# apprino.net
KiCad netlist of a schematic drawn in EAGLE
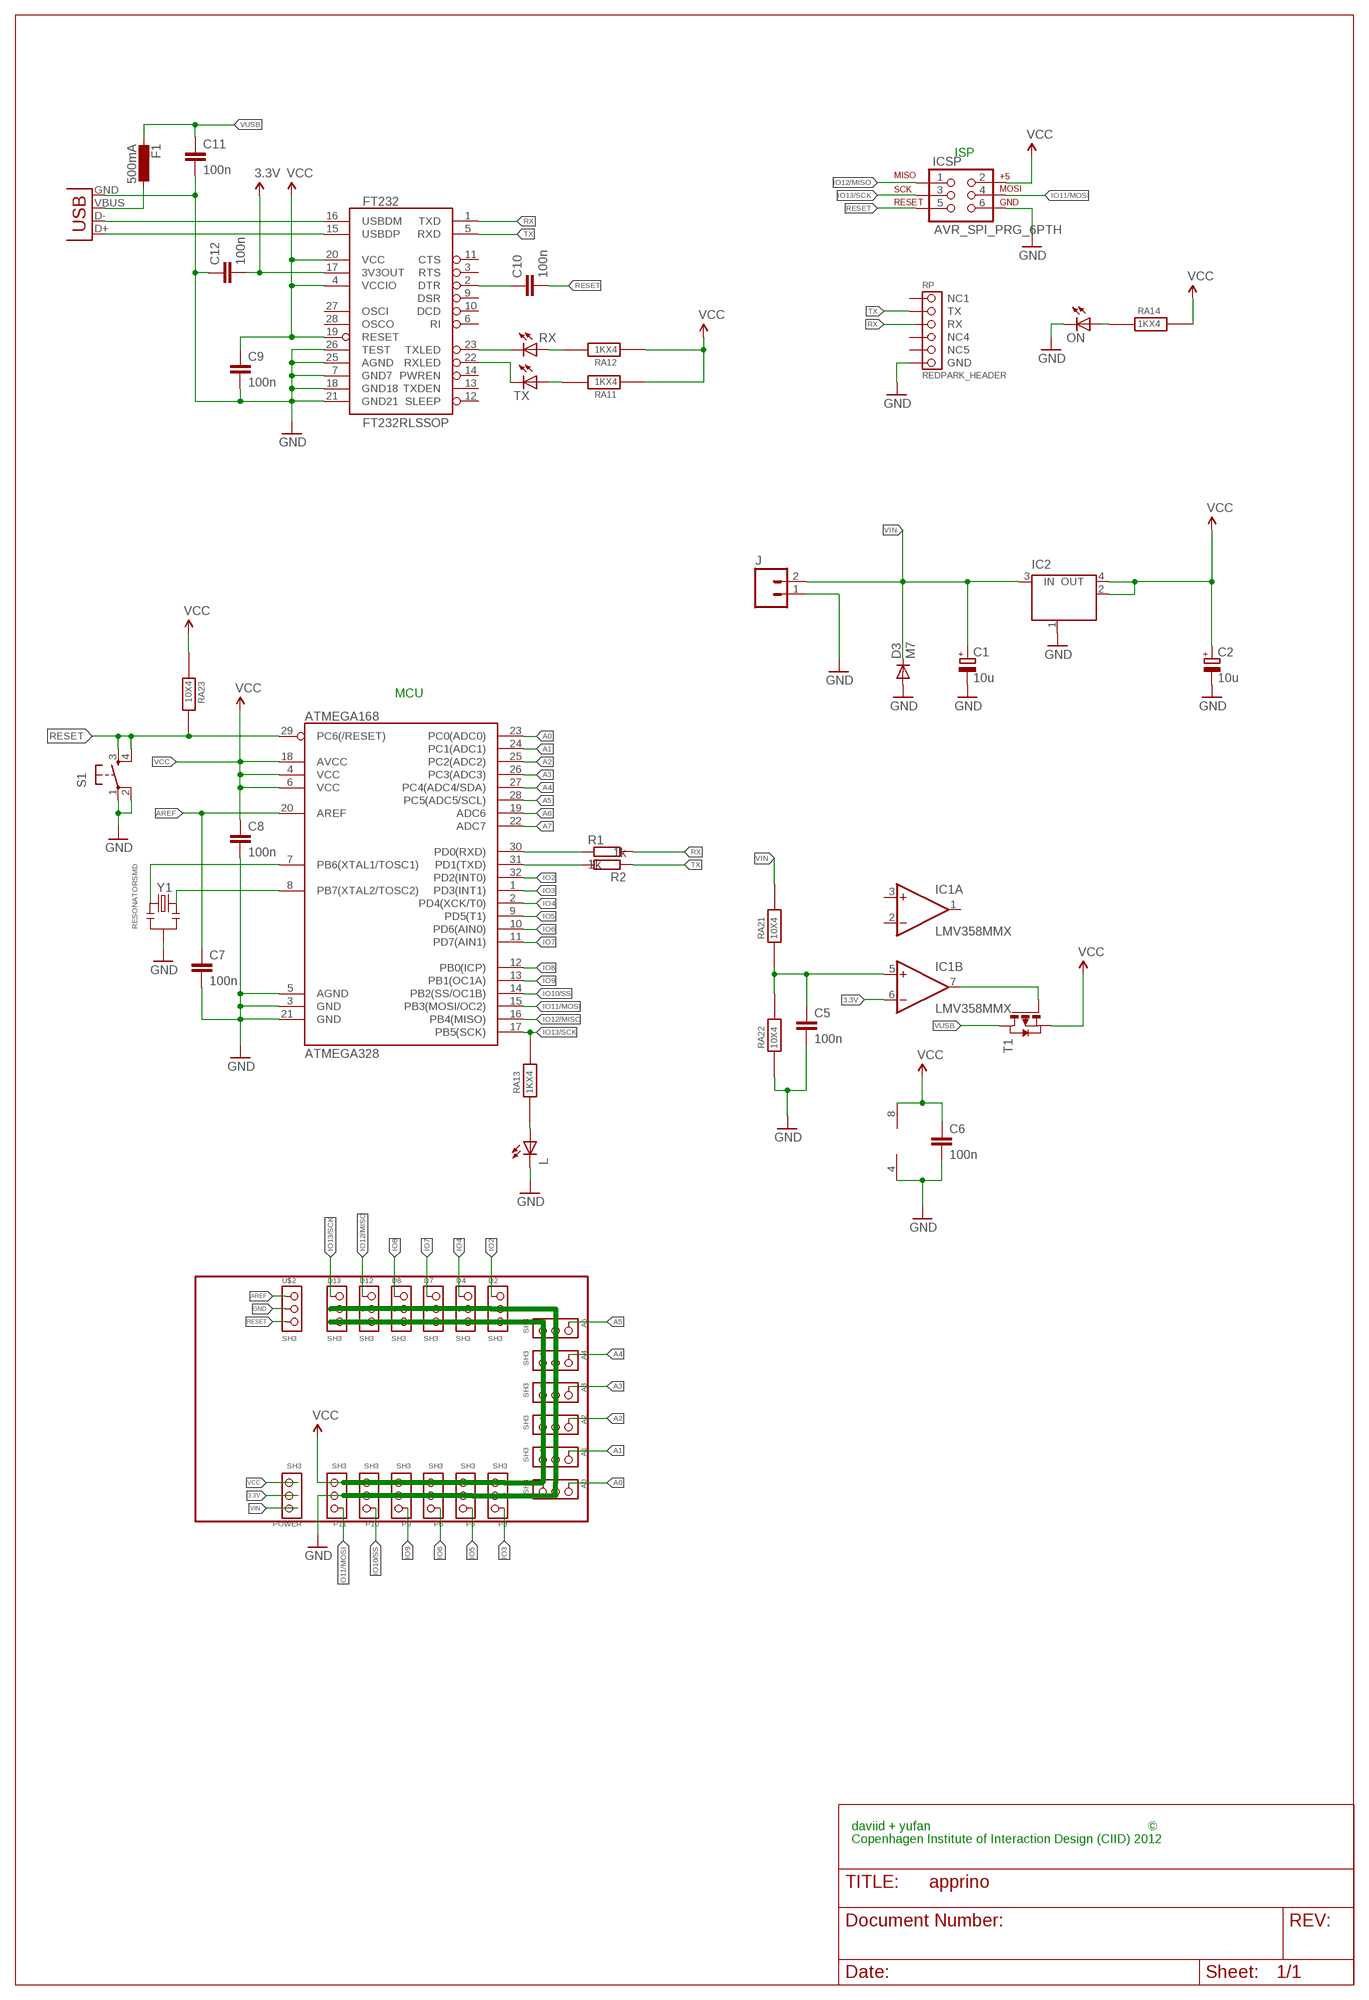
[diagram p0: schematic, sheet 1]

(export (version "E")
  (design (tool "Eeschema 10.0.6"))
  (components
    (comp (ref "A0")
      (value "SH3")
      (footprint "eagle-import:SH3")
      (libsource (lib "eagle-import") (part "SH3"))
    )
    (comp (ref "A1")
      (value "SH3")
      (footprint "eagle-import:SH3")
      (libsource (lib "eagle-import") (part "SH3"))
    )
    (comp (ref "A2")
      (value "SH3")
      (footprint "eagle-import:SH3")
      (libsource (lib "eagle-import") (part "SH3"))
    )
    (comp (ref "A3")
      (value "SH3")
      (footprint "eagle-import:SH3")
      (libsource (lib "eagle-import") (part "SH3"))
    )
    (comp (ref "A4")
      (value "SH3")
      (footprint "eagle-import:SH3")
      (libsource (lib "eagle-import") (part "SH3"))
    )
    (comp (ref "A5")
      (value "SH3")
      (footprint "eagle-import:SH3")
      (libsource (lib "eagle-import") (part "SH3"))
    )
    (comp (ref "ATMEGA328")
      (value "ATMEGA168")
      (footprint "eagle-import:TQFP32-08")
      (libsource (lib "eagle-import") (part "ATMEGA168"))
    )
    (comp (ref "C1")
      (value "10u")
      (footprint "eagle-import:SMC_B")
      (libsource (lib "eagle-import") (part "CPOL-EUSMCB"))
    )
    (comp (ref "C2")
      (value "10u")
      (footprint "eagle-import:SMC_B")
      (libsource (lib "eagle-import") (part "CPOL-EUSMCB"))
    )
    (comp (ref "C5")
      (value "100n")
      (footprint "eagle-import:C0805")
      (libsource (lib "eagle-import") (part "C-EUC0805"))
    )
    (comp (ref "C6")
      (value "100n")
      (footprint "eagle-import:C0805")
      (libsource (lib "eagle-import") (part "C-EUC0805"))
    )
    (comp (ref "C7")
      (value "100n")
      (footprint "eagle-import:C0805")
      (libsource (lib "eagle-import") (part "C-EUC0805"))
    )
    (comp (ref "C8")
      (value "100n")
      (footprint "eagle-import:C0805")
      (libsource (lib "eagle-import") (part "C-EUC0805"))
    )
    (comp (ref "C9")
      (value "100n")
      (footprint "eagle-import:C0805")
      (libsource (lib "eagle-import") (part "C-EUC0805"))
    )
    (comp (ref "C10")
      (value "100n")
      (footprint "eagle-import:C0805")
      (libsource (lib "eagle-import") (part "C-EUC0805"))
    )
    (comp (ref "C11")
      (value "100n")
      (footprint "eagle-import:C0805")
      (libsource (lib "eagle-import") (part "C-EUC0805"))
    )
    (comp (ref "C12")
      (value "100n")
      (footprint "eagle-import:C0805")
      (libsource (lib "eagle-import") (part "C-EUC0805"))
    )
    (comp (ref "D2")
      (value "SH3")
      (footprint "eagle-import:SH3")
      (libsource (lib "eagle-import") (part "SH3"))
    )
    (comp (ref "D3")
      (value "M7")
      (footprint "eagle-import:SMB")
      (libsource (lib "eagle-import") (part "DIODE-SMB"))
    )
    (comp (ref "D4")
      (value "SH3")
      (footprint "eagle-import:SH3")
      (libsource (lib "eagle-import") (part "SH3"))
    )
    (comp (ref "D7")
      (value "SH3")
      (footprint "eagle-import:SH3")
      (libsource (lib "eagle-import") (part "SH3"))
    )
    (comp (ref "D8")
      (value "SH3")
      (footprint "eagle-import:SH3")
      (libsource (lib "eagle-import") (part "SH3"))
    )
    (comp (ref "D12")
      (value "SH3")
      (footprint "eagle-import:SH3")
      (libsource (lib "eagle-import") (part "SH3"))
    )
    (comp (ref "D13")
      (value "SH3")
      (footprint "eagle-import:SH3")
      (libsource (lib "eagle-import") (part "SH3"))
    )
    (comp (ref "F1")
      (value "500mA")
      (footprint "eagle-import:L1812")
      (libsource (lib "eagle-import") (part "L-EUL1812"))
    )
    (comp (ref "FT232")
      (value "FT232RLSSOP")
      (footprint "eagle-import:SSOP28DB")
      (libsource (lib "eagle-import") (part "FT232RLSSOP"))
    )
    (comp (ref "IC1")
      (value "LMV358MMX")
      (footprint "eagle-import:MSOP08")
      (libsource (lib "eagle-import") (part "LMV358?MMX"))
    )
    (comp (ref "IC2")
      (value "MC33269ST-3.3T3")
      (footprint "eagle-import:SOT223")
      (libsource (lib "eagle-import") (part "MC33269ST-3.3T3"))
    )
    (comp (ref "ICSP")
      (value "AVR_SPI_PRG_6PTH")
      (footprint "eagle-import:2X3")
      (libsource (lib "eagle-import") (part "AVR_SPI_PRG_6PTH"))
    )
    (comp (ref "J")
      (value "M02-JST-2MM-SMT")
      (footprint "eagle-import:JST-2-SMD")
      (libsource (lib "eagle-import") (part "M02-JST-2MM-SMT"))
    )
    (comp (ref "L")
      (value "LEDCHIP-LED0805")
      (footprint "eagle-import:CHIP-LED0805")
      (libsource (lib "eagle-import") (part "LEDCHIP-LED0805"))
    )
    (comp (ref "ON")
      (value "LEDCHIP-LED0805")
      (footprint "eagle-import:CHIP-LED0805")
      (libsource (lib "eagle-import") (part "LEDCHIP-LED0805"))
    )
    (comp (ref "P3")
      (value "SH3")
      (footprint "eagle-import:SH3")
      (libsource (lib "eagle-import") (part "SH3"))
    )
    (comp (ref "P5")
      (value "SH3")
      (footprint "eagle-import:SH3")
      (libsource (lib "eagle-import") (part "SH3"))
    )
    (comp (ref "P6")
      (value "SH3")
      (footprint "eagle-import:SH3")
      (libsource (lib "eagle-import") (part "SH3"))
    )
    (comp (ref "P9")
      (value "SH3")
      (footprint "eagle-import:SH3")
      (libsource (lib "eagle-import") (part "SH3"))
    )
    (comp (ref "P10")
      (value "SH3")
      (footprint "eagle-import:SH3")
      (libsource (lib "eagle-import") (part "SH3"))
    )
    (comp (ref "P11")
      (value "SH3")
      (footprint "eagle-import:SH3")
      (libsource (lib "eagle-import") (part "SH3"))
    )
    (comp (ref "POWER")
      (value "SH3")
      (footprint "eagle-import:SH3")
      (libsource (lib "eagle-import") (part "SH3"))
    )
    (comp (ref "R1")
      (value "1k")
      (footprint "eagle-import:M0805")
      (libsource (lib "eagle-import") (part "R-EU_M0805"))
    )
    (comp (ref "R2")
      (value "1k")
      (footprint "eagle-import:M0805")
      (libsource (lib "eagle-import") (part "R-EU_M0805"))
    )
    (comp (ref "RA1")
      (value "1KX4")
      (footprint "eagle-import:R4ARRAY")
      (libsource (lib "eagle-import") (part "1KX4"))
    )
    (comp (ref "RA2")
      (value "10X4")
      (footprint "eagle-import:R4ARRAY")
      (libsource (lib "eagle-import") (part "10X4"))
    )
    (comp (ref "RP")
      (value "REDPARK_HEADER")
      (footprint "eagle-import:REDPARK_HEADER")
      (libsource (lib "eagle-import") (part "REDPARK_HEADER"))
    )
    (comp (ref "RX")
      (value "LEDCHIP-LED0805")
      (footprint "eagle-import:CHIP-LED0805")
      (libsource (lib "eagle-import") (part "LEDCHIP-LED0805"))
    )
    (comp (ref "S1")
      (value "TAC_SWITCHSMD")
      (footprint "eagle-import:TACTILE_SWITCH_SMD")
      (libsource (lib "eagle-import") (part "TAC_SWITCHSMD"))
    )
    (comp (ref "T1")
      (value "PMOSSOT23")
      (footprint "eagle-import:SOT-23")
      (libsource (lib "eagle-import") (part "PMOSSOT23"))
    )
    (comp (ref "TX")
      (value "LEDCHIP-LED0805")
      (footprint "eagle-import:CHIP-LED0805")
      (libsource (lib "eagle-import") (part "LEDCHIP-LED0805"))
    )
    (comp (ref "U$2")
      (value "SH3")
      (footprint "eagle-import:SH3")
      (libsource (lib "eagle-import") (part "SH3"))
    )
    (comp (ref "USB")
      (value "USB-MICROB")
      (footprint "eagle-import:USB-MICROB")
      (libsource (lib "eagle-import") (part "USB-MICROB"))
    )
    (comp (ref "Y1")
      (value "RESONATORSMD")
      (footprint "eagle-import:RESONATOR-SMD")
      (libsource (lib "eagle-import") (part "RESONATORSMD"))
    )
  )
  (nets
    (net (code "1") (name "3.3V") (class "Default")
      (node (ref "C12") (pin "2") (pinfunction "2_2") (pintype "passive"))
      (node (ref "FT232") (pin "17") (pinfunction "3V3OUT_17") (pintype "output"))
      (node (ref "IC1") (pin "6") (pinfunction "-IN_6") (pintype "input"))
      (node (ref "POWER") (pin "-") (pinfunction "2_-") (pintype "bidirectional"))
    )
    (net (code "2") (name "A0") (class "Default")
      (node (ref "A0") (pin "S") (pinfunction "1_S") (pintype "bidirectional"))
      (node (ref "ATMEGA328") (pin "23") (pinfunction "PC0(ADC0)_23") (pintype "bidirectional"))
    )
    (net (code "3") (name "A1") (class "Default")
      (node (ref "A1") (pin "S") (pinfunction "1_S") (pintype "bidirectional"))
      (node (ref "ATMEGA328") (pin "24") (pinfunction "PC1(ADC1)_24") (pintype "bidirectional"))
    )
    (net (code "4") (name "A2") (class "Default")
      (node (ref "A2") (pin "S") (pinfunction "1_S") (pintype "bidirectional"))
      (node (ref "ATMEGA328") (pin "25") (pinfunction "PC2(ADC2)_25") (pintype "bidirectional"))
    )
    (net (code "5") (name "A3") (class "Default")
      (node (ref "A3") (pin "S") (pinfunction "1_S") (pintype "bidirectional"))
      (node (ref "ATMEGA328") (pin "26") (pinfunction "PC3(ADC3)_26") (pintype "bidirectional"))
    )
    (net (code "6") (name "A4") (class "Default")
      (node (ref "A4") (pin "S") (pinfunction "1_S") (pintype "bidirectional"))
      (node (ref "ATMEGA328") (pin "27") (pinfunction "PC4(ADC4/SDA)_27") (pintype "bidirectional"))
    )
    (net (code "7") (name "A5") (class "Default")
      (node (ref "A5") (pin "S") (pinfunction "1_S") (pintype "bidirectional"))
      (node (ref "ATMEGA328") (pin "28") (pinfunction "PC5(ADC5/SCL)_28") (pintype "bidirectional"))
    )
    (net (code "8") (name "A6") (class "Default")
      (node (ref "ATMEGA328") (pin "19") (pinfunction "ADC6_19") (pintype "bidirectional"))
    )
    (net (code "9") (name "A7") (class "Default")
      (node (ref "ATMEGA328") (pin "22") (pinfunction "ADC7_22") (pintype "bidirectional"))
    )
    (net (code "10") (name "AREF") (class "Default")
      (node (ref "ATMEGA328") (pin "20") (pinfunction "AREF_20") (pintype "bidirectional"))
      (node (ref "C7") (pin "1") (pinfunction "1_1") (pintype "passive"))
      (node (ref "U$2") (pin "S") (pinfunction "1_S") (pintype "bidirectional"))
    )
    (net (code "11") (name "GND") (class "Default")
      (node (ref "A0") (pin "-") (pinfunction "2_-") (pintype "bidirectional"))
      (node (ref "A1") (pin "-") (pinfunction "2_-") (pintype "bidirectional"))
      (node (ref "A2") (pin "-") (pinfunction "2_-") (pintype "bidirectional"))
      (node (ref "A3") (pin "-") (pinfunction "2_-") (pintype "bidirectional"))
      (node (ref "A4") (pin "-") (pinfunction "2_-") (pintype "bidirectional"))
      (node (ref "A5") (pin "-") (pinfunction "2_-") (pintype "bidirectional"))
      (node (ref "ATMEGA328") (pin "21") (pinfunction "GND_21") (pintype "bidirectional"))
      (node (ref "ATMEGA328") (pin "3") (pinfunction "GND_3") (pintype "bidirectional"))
      (node (ref "ATMEGA328") (pin "5") (pinfunction "AGND_5") (pintype "bidirectional"))
      (node (ref "C1") (pin "-") (pinfunction "-_-") (pintype "passive"))
      (node (ref "C11") (pin "2") (pinfunction "2_2") (pintype "passive"))
      (node (ref "C12") (pin "1") (pinfunction "1_1") (pintype "passive"))
      (node (ref "C2") (pin "-") (pinfunction "-_-") (pintype "passive"))
      (node (ref "C5") (pin "2") (pinfunction "2_2") (pintype "passive"))
      (node (ref "C6") (pin "2") (pinfunction "2_2") (pintype "passive"))
      (node (ref "C7") (pin "2") (pinfunction "2_2") (pintype "passive"))
      (node (ref "C8") (pin "2") (pinfunction "2_2") (pintype "passive"))
      (node (ref "C9") (pin "2") (pinfunction "2_2") (pintype "passive"))
      (node (ref "D12") (pin "-") (pinfunction "2_-") (pintype "bidirectional"))
      (node (ref "D13") (pin "-") (pinfunction "2_-") (pintype "bidirectional"))
      (node (ref "D2") (pin "-") (pinfunction "2_-") (pintype "bidirectional"))
      (node (ref "D3") (pin "A") (pinfunction "A_A") (pintype "passive"))
      (node (ref "D4") (pin "-") (pinfunction "2_-") (pintype "bidirectional"))
      (node (ref "D7") (pin "-") (pinfunction "2_-") (pintype "bidirectional"))
      (node (ref "D8") (pin "-") (pinfunction "2_-") (pintype "bidirectional"))
      (node (ref "FT232") (pin "18") (pinfunction "GND18_18") (pintype "power_in"))
      (node (ref "FT232") (pin "21") (pinfunction "GND21_21") (pintype "power_in"))
      (node (ref "FT232") (pin "25") (pinfunction "AGND_25") (pintype "power_in"))
      (node (ref "FT232") (pin "26") (pinfunction "TEST_26") (pintype "input"))
      (node (ref "FT232") (pin "7") (pinfunction "GND7_7") (pintype "power_in"))
      (node (ref "IC1") (pin "4") (pinfunction "V-_4") (pintype "power_in"))
      (node (ref "IC2") (pin "1") (pinfunction "GND/ADJ_1") (pintype "input"))
      (node (ref "ICSP") (pin "6") (pinfunction "6_6") (pintype "passive"))
      (node (ref "J") (pin "1") (pinfunction "1_1") (pintype "passive"))
      (node (ref "L") (pin "C") (pinfunction "C_C") (pintype "passive"))
      (node (ref "ON") (pin "C") (pinfunction "C_C") (pintype "passive"))
      (node (ref "P10") (pin "-") (pinfunction "2_-") (pintype "bidirectional"))
      (node (ref "P11") (pin "-") (pinfunction "2_-") (pintype "bidirectional"))
      (node (ref "P3") (pin "-") (pinfunction "2_-") (pintype "bidirectional"))
      (node (ref "P5") (pin "-") (pinfunction "2_-") (pintype "bidirectional"))
      (node (ref "P6") (pin "-") (pinfunction "2_-") (pintype "bidirectional"))
      (node (ref "P9") (pin "-") (pinfunction "2_-") (pintype "bidirectional"))
      (node (ref "RA2") (pin "2") (pinfunction "1_2") (pintype "bidirectional"))
      (node (ref "RP") (pin "6") (pinfunction "GND_6") (pintype "bidirectional"))
      (node (ref "S1") (pin "1") (pinfunction "1_1") (pintype "passive"))
      (node (ref "S1") (pin "2") (pinfunction "2_2") (pintype "passive"))
      (node (ref "U$2") (pin "-") (pinfunction "2_-") (pintype "bidirectional"))
      (node (ref "USB") (pin "GND") (pinfunction "GND_GND") (pintype "bidirectional"))
      (node (ref "Y1") (pin "2") (pinfunction "2_2") (pintype "passive"))
    )
    (net (code "12") (name "IO2") (class "Default")
      (node (ref "ATMEGA328") (pin "32") (pinfunction "PD2(INT0)_32") (pintype "bidirectional"))
      (node (ref "D2") (pin "S") (pinfunction "1_S") (pintype "bidirectional"))
    )
    (net (code "13") (name "IO3") (class "Default")
      (node (ref "ATMEGA328") (pin "1") (pinfunction "PD3(INT1)_1") (pintype "bidirectional"))
      (node (ref "P3") (pin "S") (pinfunction "1_S") (pintype "bidirectional"))
    )
    (net (code "14") (name "IO4") (class "Default")
      (node (ref "ATMEGA328") (pin "2") (pinfunction "PD4(XCK/T0)_2") (pintype "bidirectional"))
      (node (ref "D4") (pin "S") (pinfunction "1_S") (pintype "bidirectional"))
    )
    (net (code "15") (name "IO5") (class "Default")
      (node (ref "ATMEGA328") (pin "9") (pinfunction "PD5(T1)_9") (pintype "bidirectional"))
      (node (ref "P5") (pin "S") (pinfunction "1_S") (pintype "bidirectional"))
    )
    (net (code "16") (name "IO6") (class "Default")
      (node (ref "ATMEGA328") (pin "10") (pinfunction "PD6(AIN0)_10") (pintype "bidirectional"))
      (node (ref "P6") (pin "S") (pinfunction "1_S") (pintype "bidirectional"))
    )
    (net (code "17") (name "IO7") (class "Default")
      (node (ref "ATMEGA328") (pin "11") (pinfunction "PD7(AIN1)_11") (pintype "bidirectional"))
      (node (ref "D7") (pin "S") (pinfunction "1_S") (pintype "bidirectional"))
    )
    (net (code "18") (name "IO8") (class "Default")
      (node (ref "ATMEGA328") (pin "12") (pinfunction "PB0(ICP)_12") (pintype "bidirectional"))
      (node (ref "D8") (pin "S") (pinfunction "1_S") (pintype "bidirectional"))
    )
    (net (code "19") (name "IO9") (class "Default")
      (node (ref "ATMEGA328") (pin "13") (pinfunction "PB1(OC1A)_13") (pintype "bidirectional"))
      (node (ref "P9") (pin "S") (pinfunction "1_S") (pintype "bidirectional"))
    )
    (net (code "20") (name "IO10{slash}SS") (class "Default")
      (node (ref "ATMEGA328") (pin "14") (pinfunction "PB2(SS/OC1B)_14") (pintype "bidirectional"))
      (node (ref "P10") (pin "S") (pinfunction "1_S") (pintype "bidirectional"))
    )
    (net (code "21") (name "IO11{slash}MOSI") (class "Default")
      (node (ref "ATMEGA328") (pin "15") (pinfunction "PB3(MOSI/OC2)_15") (pintype "bidirectional"))
      (node (ref "ICSP") (pin "4") (pinfunction "4_4") (pintype "passive"))
      (node (ref "P11") (pin "S") (pinfunction "1_S") (pintype "bidirectional"))
    )
    (net (code "22") (name "IO12{slash}MISO") (class "Default")
      (node (ref "ATMEGA328") (pin "16") (pinfunction "PB4(MISO)_16") (pintype "bidirectional"))
      (node (ref "D12") (pin "S") (pinfunction "1_S") (pintype "bidirectional"))
      (node (ref "ICSP") (pin "1") (pinfunction "1_1") (pintype "passive"))
    )
    (net (code "23") (name "IO13{slash}SCK") (class "Default")
      (node (ref "ATMEGA328") (pin "17") (pinfunction "PB5(SCK)_17") (pintype "bidirectional"))
      (node (ref "D13") (pin "S") (pinfunction "1_S") (pintype "bidirectional"))
      (node (ref "ICSP") (pin "3") (pinfunction "3_3") (pintype "passive"))
      (node (ref "RA1") (pin "6") (pinfunction "2_6") (pintype "bidirectional"))
    )
    (net (code "24") (name "Net-(ATMEGA328-PB6(XTAL1{slash}TOSC1))") (class "Default")
      (node (ref "ATMEGA328") (pin "7") (pinfunction "PB6(XTAL1/TOSC1)_7") (pintype "bidirectional"))
      (node (ref "Y1") (pin "1") (pinfunction "1_1") (pintype "passive"))
    )
    (net (code "25") (name "Net-(ATMEGA328-PB7(XTAL2{slash}TOSC2))") (class "Default")
      (node (ref "ATMEGA328") (pin "8") (pinfunction "PB7(XTAL2/TOSC2)_8") (pintype "bidirectional"))
      (node (ref "Y1") (pin "3") (pinfunction "3_3") (pintype "passive"))
    )
    (net (code "26") (name "Net-(ATMEGA328-PD0(RXD))") (class "Default")
      (node (ref "ATMEGA328") (pin "30") (pinfunction "PD0(RXD)_30") (pintype "bidirectional"))
      (node (ref "R1") (pin "1") (pinfunction "1_1") (pintype "passive"))
    )
    (net (code "27") (name "Net-(ATMEGA328-PD1(TXD))") (class "Default")
      (node (ref "ATMEGA328") (pin "31") (pinfunction "PD1(TXD)_31") (pintype "bidirectional"))
      (node (ref "R2") (pin "2") (pinfunction "2_2") (pintype "passive"))
    )
    (net (code "28") (name "Net-(F1-Pad1)") (class "Default")
      (node (ref "F1") (pin "1") (pinfunction "1_1") (pintype "passive"))
      (node (ref "USB") (pin "VBUS") (pinfunction "VBUS_VBUS") (pintype "bidirectional"))
    )
    (net (code "29") (name "Net-(FT232-DTR)") (class "Default")
      (node (ref "C10") (pin "1") (pinfunction "1_1") (pintype "passive"))
      (node (ref "FT232") (pin "2") (pinfunction "DTR_2") (pintype "output"))
    )
    (net (code "30") (name "Net-(FT232-RXLED)") (class "Default")
      (node (ref "FT232") (pin "22") (pinfunction "RXLED_22") (pintype "input"))
      (node (ref "TX") (pin "C") (pinfunction "C_C") (pintype "passive"))
    )
    (net (code "31") (name "Net-(FT232-TXLED)") (class "Default")
      (node (ref "FT232") (pin "23") (pinfunction "TXLED_23") (pintype "input"))
      (node (ref "RX") (pin "C") (pinfunction "C_C") (pintype "passive"))
    )
    (net (code "32") (name "Net-(FT232-USBDM)") (class "Default")
      (node (ref "FT232") (pin "16") (pinfunction "USBDM_16") (pintype "bidirectional"))
      (node (ref "USB") (pin "D-") (pinfunction "D-_D-") (pintype "bidirectional"))
    )
    (net (code "33") (name "Net-(FT232-USBDP)") (class "Default")
      (node (ref "FT232") (pin "15") (pinfunction "USBDP_15") (pintype "bidirectional"))
      (node (ref "USB") (pin "D+") (pinfunction "D+_D+") (pintype "bidirectional"))
    )
    (net (code "34") (name "Net-(IC1B-+IN)") (class "Default")
      (node (ref "C5") (pin "1") (pinfunction "1_1") (pintype "passive"))
      (node (ref "IC1") (pin "5") (pinfunction "+IN_5") (pintype "input"))
      (node (ref "RA2") (pin "1") (pinfunction "1_1") (pintype "bidirectional"))
      (node (ref "RA2") (pin "7") (pinfunction "2_7") (pintype "bidirectional"))
    )
    (net (code "35") (name "Net-(IC1B-OUT)") (class "Default")
      (node (ref "IC1") (pin "7") (pinfunction "OUT_7") (pintype "output"))
      (node (ref "T1") (pin "3") (pinfunction "G_3") (pintype "passive"))
    )
    (net (code "36") (name "Net-(RA1A-2)") (class "Default")
      (node (ref "RA1") (pin "8") (pinfunction "2_8") (pintype "bidirectional"))
      (node (ref "TX") (pin "A") (pinfunction "A_A") (pintype "passive"))
    )
    (net (code "37") (name "Net-(RA1B-2)") (class "Default")
      (node (ref "RA1") (pin "7") (pinfunction "2_7") (pintype "bidirectional"))
      (node (ref "RX") (pin "A") (pinfunction "A_A") (pintype "passive"))
    )
    (net (code "38") (name "Net-(RA1C-1)") (class "Default")
      (node (ref "L") (pin "A") (pinfunction "A_A") (pintype "passive"))
      (node (ref "RA1") (pin "3") (pinfunction "1_3") (pintype "bidirectional"))
    )
    (net (code "39") (name "Net-(RA1D-1)") (class "Default")
      (node (ref "ON") (pin "A") (pinfunction "A_A") (pintype "passive"))
      (node (ref "RA1") (pin "4") (pinfunction "1_4") (pintype "bidirectional"))
    )
    (net (code "40") (name "RESET") (class "Default")
      (node (ref "ATMEGA328") (pin "29") (pinfunction "PC6(/RESET)_29") (pintype "bidirectional"))
      (node (ref "C10") (pin "2") (pinfunction "2_2") (pintype "passive"))
      (node (ref "ICSP") (pin "5") (pinfunction "5_5") (pintype "passive"))
      (node (ref "RA2") (pin "6") (pinfunction "2_6") (pintype "bidirectional"))
      (node (ref "S1") (pin "3") (pinfunction "3_3") (pintype "passive"))
      (node (ref "S1") (pin "4") (pinfunction "4_4") (pintype "passive"))
      (node (ref "U$2") (pin "+") (pinfunction "3_+") (pintype "bidirectional"))
    )
    (net (code "41") (name "RX") (class "Default")
      (node (ref "FT232") (pin "1") (pinfunction "TXD_1") (pintype "output"))
      (node (ref "R1") (pin "2") (pinfunction "2_2") (pintype "passive"))
      (node (ref "RP") (pin "3") (pinfunction "RX_3") (pintype "bidirectional"))
    )
    (net (code "42") (name "TX") (class "Default")
      (node (ref "FT232") (pin "5") (pinfunction "RXD_5") (pintype "input"))
      (node (ref "R2") (pin "1") (pinfunction "1_1") (pintype "passive"))
      (node (ref "RP") (pin "2") (pinfunction "TX_2") (pintype "bidirectional"))
    )
    (net (code "43") (name "VCC") (class "Default")
      (node (ref "A0") (pin "+") (pinfunction "3_+") (pintype "bidirectional"))
      (node (ref "A1") (pin "+") (pinfunction "3_+") (pintype "bidirectional"))
      (node (ref "A2") (pin "+") (pinfunction "3_+") (pintype "bidirectional"))
      (node (ref "A3") (pin "+") (pinfunction "3_+") (pintype "bidirectional"))
      (node (ref "A4") (pin "+") (pinfunction "3_+") (pintype "bidirectional"))
      (node (ref "A5") (pin "+") (pinfunction "3_+") (pintype "bidirectional"))
      (node (ref "ATMEGA328") (pin "18") (pinfunction "AVCC_18") (pintype "bidirectional"))
      (node (ref "ATMEGA328") (pin "4") (pinfunction "VCC_4") (pintype "bidirectional"))
      (node (ref "ATMEGA328") (pin "6") (pinfunction "VCC_6") (pintype "bidirectional"))
      (node (ref "C2") (pin "+") (pinfunction "+_+") (pintype "passive"))
      (node (ref "C6") (pin "1") (pinfunction "1_1") (pintype "passive"))
      (node (ref "C8") (pin "1") (pinfunction "1_1") (pintype "passive"))
      (node (ref "C9") (pin "1") (pinfunction "1_1") (pintype "passive"))
      (node (ref "D12") (pin "+") (pinfunction "3_+") (pintype "bidirectional"))
      (node (ref "D13") (pin "+") (pinfunction "3_+") (pintype "bidirectional"))
      (node (ref "D2") (pin "+") (pinfunction "3_+") (pintype "bidirectional"))
      (node (ref "D4") (pin "+") (pinfunction "3_+") (pintype "bidirectional"))
      (node (ref "D7") (pin "+") (pinfunction "3_+") (pintype "bidirectional"))
      (node (ref "D8") (pin "+") (pinfunction "3_+") (pintype "bidirectional"))
      (node (ref "FT232") (pin "19") (pinfunction "RESET_19") (pintype "input"))
      (node (ref "FT232") (pin "20") (pinfunction "VCC_20") (pintype "power_in"))
      (node (ref "FT232") (pin "4") (pinfunction "VCCIO_4") (pintype "power_in"))
      (node (ref "IC1") (pin "8") (pinfunction "V+_8") (pintype "power_in"))
      (node (ref "IC2") (pin "2") (pinfunction "OUT_2") (pintype "passive"))
      (node (ref "IC2") (pin "4") (pinfunction "OUT_4") (pintype "passive"))
      (node (ref "ICSP") (pin "2") (pinfunction "2_2") (pintype "passive"))
      (node (ref "P10") (pin "+") (pinfunction "3_+") (pintype "bidirectional"))
      (node (ref "P11") (pin "+") (pinfunction "3_+") (pintype "bidirectional"))
      (node (ref "P3") (pin "+") (pinfunction "3_+") (pintype "bidirectional"))
      (node (ref "P5") (pin "+") (pinfunction "3_+") (pintype "bidirectional"))
      (node (ref "P6") (pin "+") (pinfunction "3_+") (pintype "bidirectional"))
      (node (ref "P9") (pin "+") (pinfunction "3_+") (pintype "bidirectional"))
      (node (ref "POWER") (pin "+") (pinfunction "3_+") (pintype "bidirectional"))
      (node (ref "RA1") (pin "1") (pinfunction "1_1") (pintype "bidirectional"))
      (node (ref "RA1") (pin "2") (pinfunction "1_2") (pintype "bidirectional"))
      (node (ref "RA1") (pin "5") (pinfunction "2_5") (pintype "bidirectional"))
      (node (ref "RA2") (pin "3") (pinfunction "1_3") (pintype "bidirectional"))
      (node (ref "T1") (pin "2") (pinfunction "S_2") (pintype "passive"))
    )
    (net (code "44") (name "VIN") (class "Default")
      (node (ref "C1") (pin "+") (pinfunction "+_+") (pintype "passive"))
      (node (ref "D3") (pin "C") (pinfunction "C_C") (pintype "passive"))
      (node (ref "IC2") (pin "3") (pinfunction "IN_3") (pintype "input"))
      (node (ref "J") (pin "2") (pinfunction "2_2") (pintype "passive"))
      (node (ref "POWER") (pin "S") (pinfunction "1_S") (pintype "bidirectional"))
      (node (ref "RA2") (pin "8") (pinfunction "2_8") (pintype "bidirectional"))
    )
    (net (code "45") (name "VUSB") (class "Default")
      (node (ref "C11") (pin "1") (pinfunction "1_1") (pintype "passive"))
      (node (ref "F1") (pin "2") (pinfunction "2_2") (pintype "passive"))
      (node (ref "T1") (pin "1") (pinfunction "D_1") (pintype "passive"))
    )
    (net (code "46") (name "unconnected-(FT232-CTS-Pad11)") (class "Default")
      (node (ref "FT232") (pin "11") (pinfunction "CTS_11") (pintype "input"))
    )
    (net (code "47") (name "unconnected-(FT232-DCD-Pad10)") (class "Default")
      (node (ref "FT232") (pin "10") (pinfunction "DCD_10") (pintype "input"))
    )
    (net (code "48") (name "unconnected-(FT232-DSR-Pad9)") (class "Default")
      (node (ref "FT232") (pin "9") (pinfunction "DSR_9") (pintype "input"))
    )
    (net (code "49") (name "unconnected-(FT232-OSCI-Pad27)") (class "Default")
      (node (ref "FT232") (pin "27") (pinfunction "OSCI_27") (pintype "input"))
    )
    (net (code "50") (name "unconnected-(FT232-OSCO-Pad28)") (class "Default")
      (node (ref "FT232") (pin "28") (pinfunction "OSCO_28") (pintype "output"))
    )
    (net (code "51") (name "unconnected-(FT232-PWREN-Pad14)") (class "Default")
      (node (ref "FT232") (pin "14") (pinfunction "PWREN_14") (pintype "input"))
    )
    (net (code "52") (name "unconnected-(FT232-RI-Pad6)") (class "Default")
      (node (ref "FT232") (pin "6") (pinfunction "RI_6") (pintype "input"))
    )
    (net (code "53") (name "unconnected-(FT232-RTS-Pad3)") (class "Default")
      (node (ref "FT232") (pin "3") (pinfunction "RTS_3") (pintype "output"))
    )
    (net (code "54") (name "unconnected-(FT232-SLEEP-Pad12)") (class "Default")
      (node (ref "FT232") (pin "12") (pinfunction "SLEEP_12") (pintype "input"))
    )
    (net (code "55") (name "unconnected-(FT232-TXDEN-Pad13)") (class "Default")
      (node (ref "FT232") (pin "13") (pinfunction "TXDEN_13") (pintype "input"))
    )
    (net (code "56") (name "unconnected-(IC1A-+IN-Pad3)") (class "Default")
      (node (ref "IC1") (pin "3") (pinfunction "+IN_3") (pintype "input"))
    )
    (net (code "57") (name "unconnected-(IC1A--IN-Pad2)") (class "Default")
      (node (ref "IC1") (pin "2") (pinfunction "-IN_2") (pintype "input"))
    )
    (net (code "58") (name "unconnected-(IC1A-OUT-Pad1)") (class "Default")
      (node (ref "IC1") (pin "1") (pinfunction "OUT_1") (pintype "output"))
    )
    (net (code "59") (name "unconnected-(RP-NC1-Pad1)") (class "Default")
      (node (ref "RP") (pin "1") (pinfunction "NC1_1") (pintype "bidirectional"))
    )
    (net (code "60") (name "unconnected-(RP-NC4-Pad4)") (class "Default")
      (node (ref "RP") (pin "4") (pinfunction "NC4_4") (pintype "bidirectional"))
    )
    (net (code "61") (name "unconnected-(RP-NC5-Pad5)") (class "Default")
      (node (ref "RP") (pin "5") (pinfunction "NC5_5") (pintype "bidirectional"))
    )
  )
)
